# C8T6.net
KiCad netlist of a schematic drawn in Altium Designer
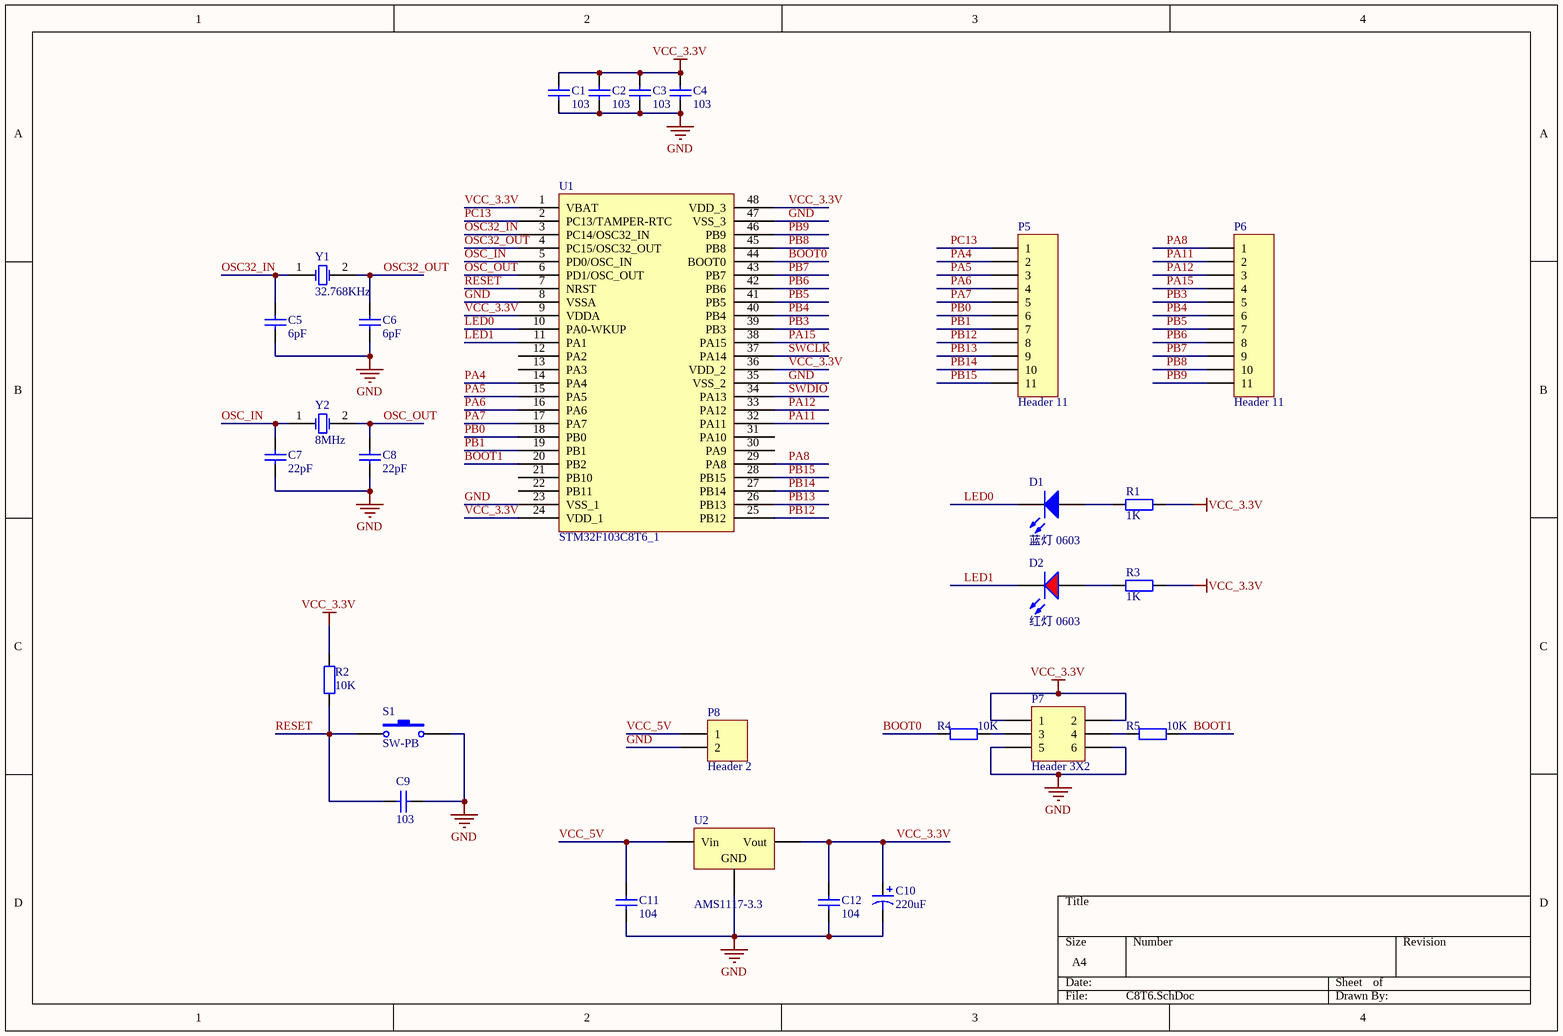
[diagram p0: C8T6.SchDoc]

(export (version "E")
  (design (tool "Eeschema 10.0.6"))
  (components
    (comp (ref "C1")
      (value "103")
      (footprint "C_0603")
      (description "Capacitor")
      (fields (field (name "Comment") "Cap") (field (name "PUBLISHER") "Altium Limited"))
      (libsource (lib "Miscellaneous Devices") (part "Cap"))
    )
    (comp (ref "C2")
      (value "103")
      (footprint "C_0603")
      (description "Capacitor")
      (fields (field (name "Comment") "Cap") (field (name "PUBLISHER") "Altium Limited"))
      (libsource (lib "Miscellaneous Devices") (part "Cap"))
    )
    (comp (ref "C3")
      (value "103")
      (footprint "C_0603")
      (description "Capacitor")
      (fields (field (name "Comment") "Cap") (field (name "PUBLISHER") "Altium Limited"))
      (libsource (lib "Miscellaneous Devices") (part "Cap"))
    )
    (comp (ref "C4")
      (value "103")
      (footprint "C_0603")
      (description "Capacitor")
      (fields (field (name "Comment") "Cap") (field (name "PUBLISHER") "Altium Limited"))
      (libsource (lib "Miscellaneous Devices") (part "Cap"))
    )
    (comp (ref "C5")
      (value "6pF")
      (footprint "C_0603")
      (description "Capacitor")
      (fields (field (name "Comment") "Cap") (field (name "PUBLISHER") "Altium Limited"))
      (libsource (lib "Miscellaneous Devices") (part "Cap"))
    )
    (comp (ref "C6")
      (value "6pF")
      (footprint "C_0603")
      (description "Capacitor")
      (fields (field (name "Comment") "Cap") (field (name "PUBLISHER") "Altium Limited"))
      (libsource (lib "Miscellaneous Devices") (part "Cap"))
    )
    (comp (ref "C7")
      (value "22pF")
      (footprint "C_0603")
      (description "Capacitor")
      (fields (field (name "Comment") "Cap") (field (name "PUBLISHER") "Altium Limited"))
      (libsource (lib "Miscellaneous Devices") (part "Cap"))
    )
    (comp (ref "C8")
      (value "22pF")
      (footprint "C_0603")
      (description "Capacitor")
      (fields (field (name "Comment") "Cap") (field (name "PUBLISHER") "Altium Limited"))
      (libsource (lib "Miscellaneous Devices") (part "Cap"))
    )
    (comp (ref "C9")
      (value "103")
      (footprint "C_0603")
      (description "Capacitor")
      (fields (field (name "Comment") "Cap") (field (name "PUBLISHER") "Altium Limited"))
      (libsource (lib "Miscellaneous Devices") (part "Cap"))
    )
    (comp (ref "C10")
      (value "220uF")
      (footprint "CAP-SMD_BD6.3-L6.6-W6.6-FD")
      (description "Polarized Capacitor (Radial)")
      (fields (field (name "Comment") "Cap Pol1") (field (name "PUBLISHER") "Altium Limited"))
      (libsource (lib "Miscellaneous Devices") (part "Cap Pol1"))
    )
    (comp (ref "C11")
      (value "104")
      (footprint "C_0603")
      (description "Capacitor")
      (fields (field (name "Comment") "Cap") (field (name "PUBLISHER") "Altium Limited"))
      (libsource (lib "Miscellaneous Devices") (part "Cap"))
    )
    (comp (ref "C12")
      (value "104")
      (footprint "C_0603")
      (description "Capacitor")
      (fields (field (name "Comment") "Cap") (field (name "PUBLISHER") "Altium Limited"))
      (libsource (lib "Miscellaneous Devices") (part "Cap"))
    )
    (comp (ref "D1")
      (value "蓝灯 0603")
      (footprint "0603_LED_S1")
      (description "发光二极管")
      (libsource (lib "JLCMiscellaneous Devices LC") (part "0603 蓝灯"))
    )
    (comp (ref "D2")
      (value "红灯 0603")
      (footprint "0603_LED_S1")
      (description "发光二极管")
      (libsource (lib "JLCMiscellaneous Devices LC") (part "0603 红灯"))
    )
    (comp (ref "P5")
      (value "Header 11")
      (footprint "HDR2.54-LI-11P")
      (description "Header, 11-Pin")
      (fields (field (name "PUBLISHER") "Altium Limited"))
      (libsource (lib "Miscellaneous Connectors") (part "Header 11"))
    )
    (comp (ref "P6")
      (value "Header 11")
      (footprint "HDR2.54-LI-11P")
      (description "Header, 11-Pin")
      (fields (field (name "PUBLISHER") "Altium Limited"))
      (libsource (lib "Miscellaneous Connectors") (part "Header 11"))
    )
    (comp (ref "P7")
      (value "Header 3X2")
      (footprint "HDR2.54-LI-2x3P")
      (description "Header, 3-Pin, Dual row")
      (fields (field (name "PUBLISHER") "Altium Limited"))
      (libsource (lib "Miscellaneous Connectors") (part "Header 3X2"))
    )
    (comp (ref "P8")
      (value "Header 2")
      (footprint "XH2.54-LI-2P")
      (description "Header, 2-Pin")
      (fields (field (name "PUBLISHER") "Altium Limited"))
      (libsource (lib "Miscellaneous Connectors") (part "Header 2"))
    )
    (comp (ref "R1")
      (value "1K")
      (footprint "R_0603")
      (description "Resistor")
      (fields (field (name "Comment") "Res2") (field (name "PUBLISHER") "Altium Limited"))
      (libsource (lib "Miscellaneous Devices") (part "Res2"))
    )
    (comp (ref "R2")
      (value "10K")
      (footprint "R_0603")
      (description "Resistor")
      (fields (field (name "Comment") "Res2") (field (name "PUBLISHER") "Altium Limited"))
      (libsource (lib "") (part "Res2_1"))
    )
    (comp (ref "R3")
      (value "1K")
      (footprint "R_0603")
      (description "Resistor")
      (fields (field (name "Comment") "Res2") (field (name "PUBLISHER") "Altium Limited"))
      (libsource (lib "Miscellaneous Devices") (part "Res2"))
    )
    (comp (ref "R4")
      (value "10K")
      (footprint "R_0603")
      (description "Resistor")
      (fields (field (name "Comment") "Res2") (field (name "PUBLISHER") "Altium Limited"))
      (libsource (lib "Miscellaneous Devices") (part "Res2"))
    )
    (comp (ref "R5")
      (value "10K")
      (footprint "R_0603")
      (description "Resistor")
      (fields (field (name "Comment") "Res2") (field (name "PUBLISHER") "Altium Limited"))
      (libsource (lib "Miscellaneous Devices") (part "Res2"))
    )
    (comp (ref "S1")
      (value "SW-PB")
      (footprint "TSW SMD-3*6*2.5")
      (description "Switch")
      (fields (field (name "PUBLISHER") "Altium Limited"))
      (libsource (lib "Miscellaneous Devices") (part "SW-PB"))
    )
    (comp (ref "U1")
      (value "STM32F103C8T6_1")
      (footprint "LQFP48-7*7")
      (libsource (lib "C8T6") (part "STM32F103C8T6_1"))
    )
    (comp (ref "U2")
      (value "AMS1117-3.3")
      (footprint "SOT-223")
      (description "低压差线性稳压(LDO)")
      (libsource (lib "JLCMiscellaneous Devices LC") (part "SOT-223 AMS1117-3.3"))
    )
    (comp (ref "Y1")
      (value "32.768KHz")
      (footprint "OSC-SMD_L3.2-W1.5")
      (description "Crystal Oscillator")
      (fields (field (name "PUBLISHER") "Altium Limited"))
      (libsource (lib "Miscellaneous Devices") (part "XTAL"))
    )
    (comp (ref "Y2")
      (value "8MHz")
      (footprint "OSC-TH_L10.0-W4.5-P5.00")
      (description "Crystal Oscillator")
      (fields (field (name "PUBLISHER") "Altium Limited"))
      (libsource (lib "Miscellaneous Devices") (part "XTAL"))
    )
  )
  (nets
    (net (code "1") (name "/BOOT0") (class "Default")
      (node (ref "R4") (pin "1") (pinfunction "1_1") (pintype "passive"))
      (node (ref "U1") (pin "44") (pinfunction "BOOT0_44") (pintype "passive"))
    )
    (net (code "2") (name "/BOOT1") (class "Default")
      (node (ref "R5") (pin "2") (pinfunction "2_2") (pintype "passive"))
      (node (ref "U1") (pin "20") (pinfunction "PB2_20") (pintype "passive"))
    )
    (net (code "3") (name "/LED0") (class "Default")
      (node (ref "D1") (pin "K") (pinfunction "K_K") (pintype "passive"))
      (node (ref "U1") (pin "10") (pinfunction "PA0-WKUP_10") (pintype "passive"))
    )
    (net (code "4") (name "/LED1") (class "Default")
      (node (ref "D2") (pin "K") (pinfunction "K_K") (pintype "passive"))
      (node (ref "U1") (pin "11") (pinfunction "PA1_11") (pintype "passive"))
    )
    (net (code "5") (name "/OSC32_IN") (class "Default")
      (node (ref "C5") (pin "2") (pinfunction "2_2") (pintype "passive"))
      (node (ref "U1") (pin "3") (pinfunction "PC14/OSC32_IN_3") (pintype "passive"))
      (node (ref "Y1") (pin "1") (pinfunction "OSC1_1") (pintype "passive"))
    )
    (net (code "6") (name "/OSC32_OUT") (class "Default")
      (node (ref "C6") (pin "2") (pinfunction "2_2") (pintype "passive"))
      (node (ref "U1") (pin "4") (pinfunction "PC15/OSC32_OUT_4") (pintype "passive"))
      (node (ref "Y1") (pin "2") (pinfunction "OSC2_2") (pintype "passive"))
    )
    (net (code "7") (name "/OSC_IN") (class "Default")
      (node (ref "C7") (pin "2") (pinfunction "2_2") (pintype "passive"))
      (node (ref "U1") (pin "5") (pinfunction "PD0/OSC_IN_5") (pintype "passive"))
      (node (ref "Y2") (pin "1") (pinfunction "OSC1_1") (pintype "passive"))
    )
    (net (code "8") (name "/OSC_OUT") (class "Default")
      (node (ref "C8") (pin "2") (pinfunction "2_2") (pintype "passive"))
      (node (ref "U1") (pin "6") (pinfunction "PD1/OSC_OUT_6") (pintype "passive"))
      (node (ref "Y2") (pin "2") (pinfunction "OSC2_2") (pintype "passive"))
    )
    (net (code "9") (name "/PA4") (class "Default")
      (node (ref "P5") (pin "2") (pinfunction "2_2") (pintype "passive"))
      (node (ref "U1") (pin "14") (pinfunction "PA4_14") (pintype "passive"))
    )
    (net (code "10") (name "/PA5") (class "Default")
      (node (ref "P5") (pin "3") (pinfunction "3_3") (pintype "passive"))
      (node (ref "U1") (pin "15") (pinfunction "PA5_15") (pintype "passive"))
    )
    (net (code "11") (name "/PA6") (class "Default")
      (node (ref "P5") (pin "4") (pinfunction "4_4") (pintype "passive"))
      (node (ref "U1") (pin "16") (pinfunction "PA6_16") (pintype "passive"))
    )
    (net (code "12") (name "/PA7") (class "Default")
      (node (ref "P5") (pin "5") (pinfunction "5_5") (pintype "passive"))
      (node (ref "U1") (pin "17") (pinfunction "PA7_17") (pintype "passive"))
    )
    (net (code "13") (name "/PA8") (class "Default")
      (node (ref "P6") (pin "1") (pinfunction "1_1") (pintype "passive"))
      (node (ref "U1") (pin "29") (pinfunction "PA8_29") (pintype "passive"))
    )
    (net (code "14") (name "/PA11") (class "Default")
      (node (ref "P6") (pin "2") (pinfunction "2_2") (pintype "passive"))
      (node (ref "U1") (pin "32") (pinfunction "PA11_32") (pintype "passive"))
    )
    (net (code "15") (name "/PA12") (class "Default")
      (node (ref "P6") (pin "3") (pinfunction "3_3") (pintype "passive"))
      (node (ref "U1") (pin "33") (pinfunction "PA12_33") (pintype "passive"))
    )
    (net (code "16") (name "/PA15") (class "Default")
      (node (ref "P6") (pin "4") (pinfunction "4_4") (pintype "passive"))
      (node (ref "U1") (pin "38") (pinfunction "PA15_38") (pintype "passive"))
    )
    (net (code "17") (name "/PB0") (class "Default")
      (node (ref "P5") (pin "6") (pinfunction "6_6") (pintype "passive"))
      (node (ref "U1") (pin "18") (pinfunction "PB0_18") (pintype "passive"))
    )
    (net (code "18") (name "/PB1") (class "Default")
      (node (ref "P5") (pin "7") (pinfunction "7_7") (pintype "passive"))
      (node (ref "U1") (pin "19") (pinfunction "PB1_19") (pintype "passive"))
    )
    (net (code "19") (name "/PB3") (class "Default")
      (node (ref "P6") (pin "5") (pinfunction "5_5") (pintype "passive"))
      (node (ref "U1") (pin "39") (pinfunction "PB3_39") (pintype "passive"))
    )
    (net (code "20") (name "/PB4") (class "Default")
      (node (ref "P6") (pin "6") (pinfunction "6_6") (pintype "passive"))
      (node (ref "U1") (pin "40") (pinfunction "PB4_40") (pintype "passive"))
    )
    (net (code "21") (name "/PB5") (class "Default")
      (node (ref "P6") (pin "7") (pinfunction "7_7") (pintype "passive"))
      (node (ref "U1") (pin "41") (pinfunction "PB5_41") (pintype "passive"))
    )
    (net (code "22") (name "/PB6") (class "Default")
      (node (ref "P6") (pin "8") (pinfunction "8_8") (pintype "passive"))
      (node (ref "U1") (pin "42") (pinfunction "PB6_42") (pintype "passive"))
    )
    (net (code "23") (name "/PB7") (class "Default")
      (node (ref "P6") (pin "9") (pinfunction "9_9") (pintype "passive"))
      (node (ref "U1") (pin "43") (pinfunction "PB7_43") (pintype "passive"))
    )
    (net (code "24") (name "/PB8") (class "Default")
      (node (ref "P6") (pin "10") (pinfunction "10_10") (pintype "passive"))
      (node (ref "U1") (pin "45") (pinfunction "PB8_45") (pintype "passive"))
    )
    (net (code "25") (name "/PB9") (class "Default")
      (node (ref "P6") (pin "11") (pinfunction "11_11") (pintype "passive"))
      (node (ref "U1") (pin "46") (pinfunction "PB9_46") (pintype "passive"))
    )
    (net (code "26") (name "/PB12") (class "Default")
      (node (ref "P5") (pin "8") (pinfunction "8_8") (pintype "passive"))
      (node (ref "U1") (pin "25") (pinfunction "PB12_25") (pintype "passive"))
    )
    (net (code "27") (name "/PB13") (class "Default")
      (node (ref "P5") (pin "9") (pinfunction "9_9") (pintype "passive"))
      (node (ref "U1") (pin "26") (pinfunction "PB13_26") (pintype "passive"))
    )
    (net (code "28") (name "/PB14") (class "Default")
      (node (ref "P5") (pin "10") (pinfunction "10_10") (pintype "passive"))
      (node (ref "U1") (pin "27") (pinfunction "PB14_27") (pintype "passive"))
    )
    (net (code "29") (name "/PB15") (class "Default")
      (node (ref "P5") (pin "11") (pinfunction "11_11") (pintype "passive"))
      (node (ref "U1") (pin "28") (pinfunction "PB15_28") (pintype "passive"))
    )
    (net (code "30") (name "/PC13") (class "Default")
      (node (ref "P5") (pin "1") (pinfunction "1_1") (pintype "passive"))
      (node (ref "U1") (pin "2") (pinfunction "PC13/TAMPER-RTC_2") (pintype "passive"))
    )
    (net (code "31") (name "/RESET") (class "Default")
      (node (ref "C9") (pin "1") (pinfunction "1_1") (pintype "passive"))
      (node (ref "R2") (pin "1") (pinfunction "1_1") (pintype "passive"))
      (node (ref "S1") (pin "1") (pinfunction "1_1") (pintype "passive"))
      (node (ref "U1") (pin "7") (pinfunction "NRST_7") (pintype "passive"))
    )
    (net (code "32") (name "/SWCLK") (class "Default")
      (node (ref "U1") (pin "37") (pinfunction "PA14_37") (pintype "passive"))
    )
    (net (code "33") (name "/SWDIO") (class "Default")
      (node (ref "U1") (pin "34") (pinfunction "PA13_34") (pintype "passive"))
    )
    (net (code "34") (name "/VCC_5V") (class "Default")
      (node (ref "C11") (pin "2") (pinfunction "2_2") (pintype "passive"))
      (node (ref "P8") (pin "1") (pinfunction "1_1") (pintype "passive"))
      (node (ref "U2") (pin "3") (pinfunction "Vin_3") (pintype "passive"))
    )
    (net (code "35") (name "GND") (class "Default")
      (node (ref "C1") (pin "1") (pinfunction "1_1") (pintype "passive"))
      (node (ref "C10") (pin "2") (pinfunction "2_2") (pintype "passive"))
      (node (ref "C11") (pin "1") (pinfunction "1_1") (pintype "passive"))
      (node (ref "C12") (pin "1") (pinfunction "1_1") (pintype "passive"))
      (node (ref "C2") (pin "1") (pinfunction "1_1") (pintype "passive"))
      (node (ref "C3") (pin "1") (pinfunction "1_1") (pintype "passive"))
      (node (ref "C4") (pin "1") (pinfunction "1_1") (pintype "passive"))
      (node (ref "C5") (pin "1") (pinfunction "1_1") (pintype "passive"))
      (node (ref "C6") (pin "1") (pinfunction "1_1") (pintype "passive"))
      (node (ref "C7") (pin "1") (pinfunction "1_1") (pintype "passive"))
      (node (ref "C8") (pin "1") (pinfunction "1_1") (pintype "passive"))
      (node (ref "C9") (pin "2") (pinfunction "2_2") (pintype "passive"))
      (node (ref "P7") (pin "5") (pinfunction "5_5") (pintype "passive"))
      (node (ref "P7") (pin "6") (pinfunction "6_6") (pintype "passive"))
      (node (ref "P8") (pin "2") (pinfunction "2_2") (pintype "passive"))
      (node (ref "S1") (pin "2") (pinfunction "2_2") (pintype "passive"))
      (node (ref "U1") (pin "23") (pinfunction "VSS_1_23") (pintype "passive"))
      (node (ref "U1") (pin "35") (pinfunction "VSS_2_35") (pintype "passive"))
      (node (ref "U1") (pin "47") (pinfunction "VSS_3_47") (pintype "passive"))
      (node (ref "U1") (pin "8") (pinfunction "VSSA_8") (pintype "passive"))
      (node (ref "U2") (pin "1") (pinfunction "GND_1") (pintype "passive"))
    )
    (net (code "36") (name "Net-(D1-PadA)") (class "Default")
      (node (ref "D1") (pin "A") (pinfunction "A_A") (pintype "passive"))
      (node (ref "R1") (pin "1") (pinfunction "1_1") (pintype "passive"))
    )
    (net (code "37") (name "Net-(D2-PadA)") (class "Default")
      (node (ref "D2") (pin "A") (pinfunction "A_A") (pintype "passive"))
      (node (ref "R3") (pin "1") (pinfunction "1_1") (pintype "passive"))
    )
    (net (code "38") (name "Net-(P7-Pad3)") (class "Default")
      (node (ref "P7") (pin "3") (pinfunction "3_3") (pintype "passive"))
      (node (ref "R4") (pin "2") (pinfunction "2_2") (pintype "passive"))
    )
    (net (code "39") (name "Net-(P7-Pad4)") (class "Default")
      (node (ref "P7") (pin "4") (pinfunction "4_4") (pintype "passive"))
      (node (ref "R5") (pin "1") (pinfunction "1_1") (pintype "passive"))
    )
    (net (code "40") (name "VCC_3.3V") (class "Default")
      (node (ref "C1") (pin "2") (pinfunction "2_2") (pintype "passive"))
      (node (ref "C10") (pin "1") (pinfunction "1_1") (pintype "passive"))
      (node (ref "C12") (pin "2") (pinfunction "2_2") (pintype "passive"))
      (node (ref "C2") (pin "2") (pinfunction "2_2") (pintype "passive"))
      (node (ref "C3") (pin "2") (pinfunction "2_2") (pintype "passive"))
      (node (ref "C4") (pin "2") (pinfunction "2_2") (pintype "passive"))
      (node (ref "P7") (pin "1") (pinfunction "1_1") (pintype "passive"))
      (node (ref "P7") (pin "2") (pinfunction "2_2") (pintype "passive"))
      (node (ref "R1") (pin "2") (pinfunction "2_2") (pintype "passive"))
      (node (ref "R2") (pin "2") (pinfunction "2_2") (pintype "passive"))
      (node (ref "R3") (pin "2") (pinfunction "2_2") (pintype "passive"))
      (node (ref "U1") (pin "1") (pinfunction "VBAT_1") (pintype "passive"))
      (node (ref "U1") (pin "24") (pinfunction "VDD_1_24") (pintype "passive"))
      (node (ref "U1") (pin "36") (pinfunction "VDD_2_36") (pintype "passive"))
      (node (ref "U1") (pin "48") (pinfunction "VDD_3_48") (pintype "passive"))
      (node (ref "U1") (pin "9") (pinfunction "VDDA_9") (pintype "passive"))
      (node (ref "U2") (pin "2") (pinfunction "Vout_2") (pintype "passive"))
    )
    (net (code "41") (name "unconnected-(U1-PA2-Pad12)") (class "Default")
      (node (ref "U1") (pin "12") (pinfunction "PA2_12") (pintype "passive"))
    )
    (net (code "42") (name "unconnected-(U1-PA3-Pad13)") (class "Default")
      (node (ref "U1") (pin "13") (pinfunction "PA3_13") (pintype "passive"))
    )
    (net (code "43") (name "unconnected-(U1-PA9-Pad30)") (class "Default")
      (node (ref "U1") (pin "30") (pinfunction "PA9_30") (pintype "passive"))
    )
    (net (code "44") (name "unconnected-(U1-PA10-Pad31)") (class "Default")
      (node (ref "U1") (pin "31") (pinfunction "PA10_31") (pintype "passive"))
    )
    (net (code "45") (name "unconnected-(U1-PB10-Pad21)") (class "Default")
      (node (ref "U1") (pin "21") (pinfunction "PB10_21") (pintype "passive"))
    )
    (net (code "46") (name "unconnected-(U1-PB11-Pad22)") (class "Default")
      (node (ref "U1") (pin "22") (pinfunction "PB11_22") (pintype "passive"))
    )
  )
)
